# PWMFanController.net
KiCad netlist of a schematic drawn in EAGLE
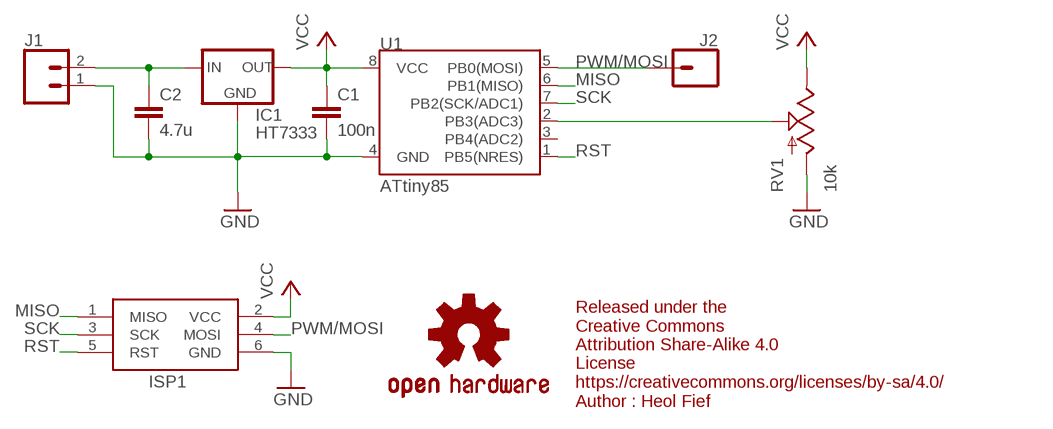
[diagram p0: schematic, sheet 1]

(export (version "E")
  (design (tool "Eeschema 10.0.6"))
  (components
    (comp (ref "C1")
      (value "100n")
      (footprint "eagle-import:C0805K")
      (libsource (lib "eagle-import") (part "C-EUC0805K"))
    )
    (comp (ref "C2")
      (value "4.7u")
      (footprint "eagle-import:C0805K")
      (libsource (lib "eagle-import") (part "C-EUC0805K"))
    )
    (comp (ref "IC1")
      (value "HT7333")
      (footprint "eagle-import:SOT-89")
      (libsource (lib "eagle-import") (part "HT7333"))
    )
    (comp (ref "ISP1")
      (value "AVRISP-6")
      (footprint "eagle-import:AVRISP")
      (libsource (lib "eagle-import") (part "AVRISP-6"))
    )
    (comp (ref "J1")
      (value "CONN_02")
      (footprint "eagle-import:1X02")
      (libsource (lib "eagle-import") (part "CONN_02"))
    )
    (comp (ref "J2")
      (value "CONN_01")
      (footprint "eagle-import:1X01")
      (libsource (lib "eagle-import") (part "CONN_01"))
    )
    (comp (ref "LOGO1")
      (value "OSHW-LOGOS-COPPER")
      (footprint "eagle-import:OSHW-LOGO-S_COPPER")
      (libsource (lib "eagle-import") (part "OSHW-LOGOS-COPPER"))
    )
    (comp (ref "RV1")
      (value "10k")
      (footprint "eagle-import:POT_MAMMOTH")
      (libsource (lib "eagle-import") (part "POTMAM"))
    )
    (comp (ref "U1")
      (value "ATtiny85")
      (footprint "eagle-import:SO08-EIAJ_MCU")
      (libsource (lib "eagle-import") (part "ATTINY45TINY85-20-SMT"))
    )
  )
  (nets
    (net (code "1") (name "/MISO") (class "Default")
      (node (ref "ISP1") (pin "1") (pinfunction "MISO_1") (pintype "input"))
      (node (ref "U1") (pin "6") (pinfunction "PB1(MISO)_6") (pintype "bidirectional"))
    )
    (net (code "2") (name "/PWM{slash}MOSI") (class "Default")
      (node (ref "ISP1") (pin "4") (pinfunction "MOSI_4") (pintype "output"))
      (node (ref "J2") (pin "1") (pinfunction "1_1") (pintype "passive"))
      (node (ref "U1") (pin "5") (pinfunction "PB0(MOSI)_5") (pintype "bidirectional"))
    )
    (net (code "3") (name "/RST") (class "Default")
      (node (ref "ISP1") (pin "5") (pinfunction "RST_5") (pintype "output"))
      (node (ref "U1") (pin "1") (pinfunction "PB5(NRES)_1") (pintype "bidirectional"))
    )
    (net (code "4") (name "/SCK") (class "Default")
      (node (ref "ISP1") (pin "3") (pinfunction "SCK_3") (pintype "output"))
      (node (ref "U1") (pin "7") (pinfunction "PB2(SCK/ADC1)_7") (pintype "bidirectional"))
    )
    (net (code "5") (name "GND") (class "Default")
      (node (ref "C1") (pin "2") (pinfunction "2_2") (pintype "passive"))
      (node (ref "C2") (pin "2") (pinfunction "2_2") (pintype "passive"))
      (node (ref "IC1") (pin "2") (pinfunction "GND_2") (pintype "input"))
      (node (ref "ISP1") (pin "6") (pinfunction "GND_6") (pintype "power_in"))
      (node (ref "J1") (pin "1") (pinfunction "1_1") (pintype "passive"))
      (node (ref "RV1") (pin "P$1") (pinfunction "A_P$1") (pintype "passive"))
      (node (ref "U1") (pin "4") (pinfunction "GND_4") (pintype "bidirectional"))
    )
    (net (code "6") (name "Net-(C2-Pad1)") (class "Default")
      (node (ref "C2") (pin "1") (pinfunction "1_1") (pintype "passive"))
      (node (ref "IC1") (pin "3") (pinfunction "IN_3") (pintype "input"))
      (node (ref "IC1") (pin "4") (pinfunction "IN_4") (pintype "input"))
      (node (ref "J1") (pin "2") (pinfunction "2_2") (pintype "passive"))
    )
    (net (code "7") (name "Net-(RV1-S)") (class "Default")
      (node (ref "RV1") (pin "P$2") (pinfunction "S_P$2") (pintype "passive"))
      (node (ref "U1") (pin "2") (pinfunction "PB3(ADC3)_2") (pintype "bidirectional"))
    )
    (net (code "8") (name "VCC") (class "Default")
      (node (ref "C1") (pin "1") (pinfunction "1_1") (pintype "passive"))
      (node (ref "IC1") (pin "1") (pinfunction "OUT_1") (pintype "passive"))
      (node (ref "ISP1") (pin "2") (pinfunction "VCC_2") (pintype "power_in"))
      (node (ref "RV1") (pin "P$3") (pinfunction "E_P$3") (pintype "passive"))
      (node (ref "U1") (pin "8") (pinfunction "VCC_8") (pintype "bidirectional"))
    )
    (net (code "9") (name "unconnected-(U1-PB4(ADC2)-Pad3)") (class "Default")
      (node (ref "U1") (pin "3") (pinfunction "PB4(ADC2)_3") (pintype "bidirectional"))
    )
  )
)
